# design.net
KiCad netlist of a schematic drawn in Altium Designer
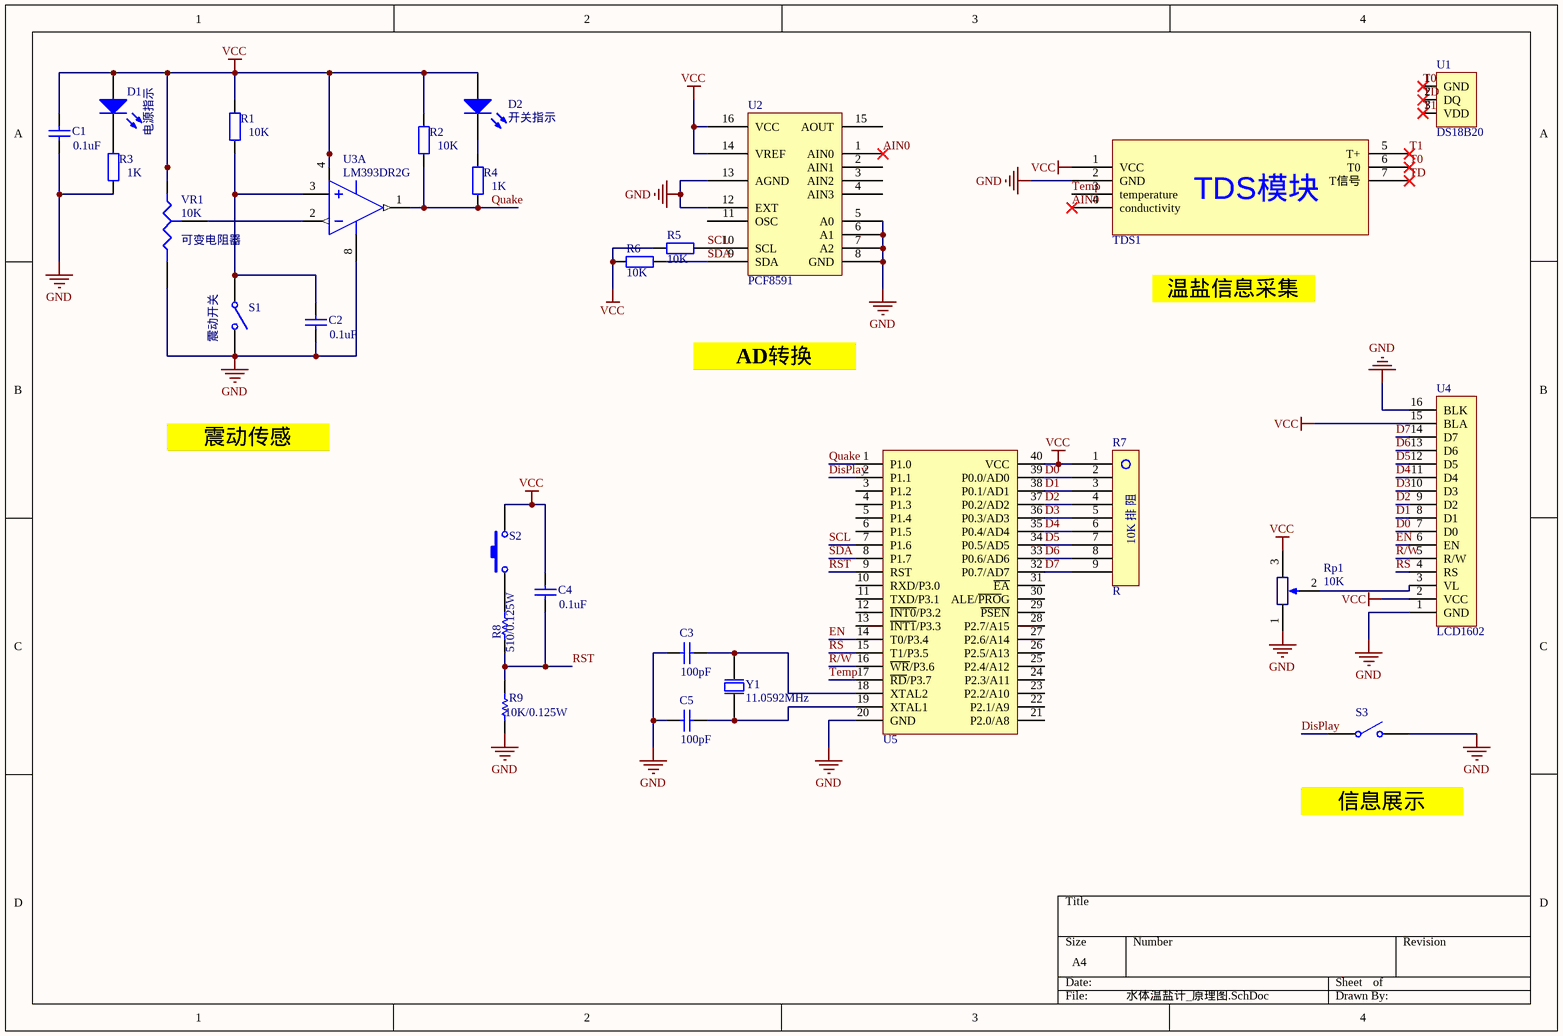
[diagram p0: 水体温盐计_原理图.SchDoc]

(export (version "E")
  (design (tool "Eeschema 10.0.6"))
  (components
    (comp (ref "C1")
      (value "0.1uF")
      (footprint "RAD-0.3")
      (description "Capacitor")
      (fields (field (name "Comment") "Cap") (field (name "PUBLISHER") "Altium Limited"))
      (libsource (lib "Miscellaneous Devices") (part "Cap"))
    )
    (comp (ref "C2")
      (value "0.1uF")
      (footprint "RAD-0.3")
      (description "Capacitor")
      (fields (field (name "Comment") "Cap") (field (name "PUBLISHER") "Altium Limited"))
      (libsource (lib "Miscellaneous Devices") (part "Cap"))
    )
    (comp (ref "C3")
      (value "100pF")
      (footprint "RAD-0.3")
      (description "Capacitor")
      (fields (field (name "Comment") "Cap") (field (name "PUBLISHER") "Altium Limited"))
      (libsource (lib "Miscellaneous Devices") (part "Cap"))
    )
    (comp (ref "C4")
      (value "0.1uF")
      (footprint "RAD-0.3")
      (description "Capacitor")
      (fields (field (name "Comment") "Cap") (field (name "PUBLISHER") "Altium Limited"))
      (libsource (lib "Miscellaneous Devices") (part "Cap"))
    )
    (comp (ref "C5")
      (value "100pF")
      (footprint "RAD-0.3")
      (description "Capacitor")
      (fields (field (name "Comment") "Cap") (field (name "PUBLISHER") "Altium Limited"))
      (libsource (lib "Miscellaneous Devices") (part "Cap"))
    )
    (comp (ref "D1")
      (value "电源指示")
      (footprint "LED-0")
      (description "Typical INFRARED GaAs LED")
      (fields (field (name "PUBLISHER") "Altium Limited"))
      (libsource (lib "Miscellaneous Devices") (part "LED0"))
    )
    (comp (ref "D2")
      (value "开关指示")
      (footprint "3.2X1.6X1.1")
      (description "Typical RED, GREEN, YELLOW, AMBER GaAs LED")
      (fields (field (name "PUBLISHER") "Altium Limited"))
      (libsource (lib "Miscellaneous Devices") (part "LED2"))
    )
    (comp (ref "R1")
      (value "10K")
      (footprint "AXIAL-0.4")
      (description "Resistor")
      (fields (field (name "Comment") "Res2") (field (name "PUBLISHER") "Altium Limited"))
      (libsource (lib "Miscellaneous Devices") (part "Res2"))
    )
    (comp (ref "R2")
      (value "10K")
      (footprint "AXIAL-0.4")
      (description "Resistor")
      (fields (field (name "Comment") "Res2") (field (name "PUBLISHER") "Altium Limited"))
      (libsource (lib "Miscellaneous Devices") (part "Res2"))
    )
    (comp (ref "R3")
      (value "1K")
      (footprint "AXIAL-0.4")
      (description "Resistor")
      (fields (field (name "Comment") "Res2") (field (name "PUBLISHER") "Altium Limited"))
      (libsource (lib "Miscellaneous Devices") (part "Res2"))
    )
    (comp (ref "R4")
      (value "1K")
      (footprint "AXIAL-0.4")
      (description "Resistor")
      (fields (field (name "Comment") "Res2") (field (name "PUBLISHER") "Altium Limited"))
      (libsource (lib "Miscellaneous Devices") (part "Res2"))
    )
    (comp (ref "R5")
      (value "10K")
      (footprint "AXIAL-0.4")
      (description "Resistor")
      (fields (field (name "Comment") "Res2") (field (name "PUBLISHER") "Altium Limited"))
      (libsource (lib "") (part "Res2_1"))
    )
    (comp (ref "R6")
      (value "10K")
      (footprint "AXIAL-0.4")
      (description "Resistor")
      (fields (field (name "Comment") "Res2") (field (name "PUBLISHER") "Altium Limited"))
      (libsource (lib "") (part "Res2_1"))
    )
    (comp (ref "R7") (value "R") (footprint "HDR1X9") (libsource (lib "原理图") (part "R")))
    (comp (ref "R8")
      (value "510/0.125W")
      (footprint "AXIAL-0.3")
      (description "Resistor")
      (fields (field (name "Comment") "Res1") (field (name "PUBLISHER") "Altium Limited"))
      (libsource (lib "Miscellaneous Devices") (part "Res1"))
    )
    (comp (ref "R9")
      (value "10K/0.125W")
      (footprint "AXIAL-0.3")
      (description "Resistor")
      (fields (field (name "Comment") "Res1") (field (name "PUBLISHER") "Altium Limited"))
      (libsource (lib "Miscellaneous Devices") (part "Res1"))
    )
    (comp (ref "Rp1")
      (value "3303X-3-502E")
      (footprint "3303X-3-502E")
      (fields (field (name "R") "10K"))
      (libsource (lib "02 Miscellaneous_Devices_ZSF_Library") (part "RP_3303X-3-502E"))
    )
    (comp (ref "S1")
      (value "震动开关")
      (footprint "SW_3-6-2.5")
      (description "Single-Pole, Single-Throw Switch")
      (fields (field (name "PUBLISHER") "Altium Limited"))
      (libsource (lib "02 Miscellaneous_Devices_ZSF_Library") (part "SW-SPST"))
    )
    (comp (ref "S2")
      (value "Tactile Switch")
      (footprint "BUTTON_6*6")
      (description "Tactile Switch触觉开关")
      (fields (field (name "PUBLISHER") "Altium Limited"))
      (libsource (lib "02 Miscellaneous_Devices_ZSF_Library") (part "SW-PB"))
    )
    (comp (ref "S3")
      (value "S")
      (footprint "SW_3-6-2.5")
      (description "Single-Pole, Single-Throw Switch")
      (fields (field (name "PUBLISHER") "Altium Limited"))
      (libsource (lib "02 Miscellaneous_Devices_ZSF_Library") (part "SW-SPST"))
    )
    (comp (ref "TDS1") (value "TDS水质传感器") (footprint "HDR1X7") (libsource (lib "原理图") (part "TDS水质传感器")))
    (comp (ref "U1")
      (value "DS18B20")
      (footprint "HDR1X3")
      (libsource (lib "02 Miscellaneous_Devices_ZSF_Library") (part "DS18B20"))
    )
    (comp (ref "U2") (value "PCF8591") (footprint "SOT403-1_M") (libsource (lib "原理图") (part "PCF8591")))
    (comp (ref "U3")
      (value "LM393DR2G")
      (footprint "SOIC-8_150mil")
      (description "电压比较器")
      (libsource (lib "02 Miscellaneous_Devices_ZSF_Library") (part "LM393DR2G"))
    )
    (comp (ref "U4")
      (value "LCD1602")
      (footprint "LCD1602")
      (libsource (lib "02 Miscellaneous_Devices_ZSF_Library") (part "LCD1602"))
    )
    (comp (ref "U5")
      (value "AT89C51")
      (footprint "DIP-40")
      (description "AT89C51_DIP40")
      (libsource (lib "02 Miscellaneous_Devices_ZSF_Library") (part "AT89C51-DIP"))
    )
    (comp (ref "VR1")
      (value "可变电阻器")
      (footprint "VR3")
      (description "Tapped Resistor")
      (fields (field (name "ALTIUM_VALUE") "10K") (field (name "PUBLISHER") "Altium Limited"))
      (libsource (lib "Miscellaneous Devices") (part "Res Tap"))
    )
    (comp (ref "Y1")
      (value "XTAL")
      (footprint "XTAL")
      (description "Crystal Oscillator")
      (fields (field (name "FREQUENCY") "11.0592MHz") (field (name "PUBLISHER") "Altium Limited"))
      (libsource (lib "03-EButterflyIntegratedLibrary") (part "XTAL"))
    )
  )
  (nets
    (net (code "1") (name "/AIN0") (class "Default")
      (node (ref "TDS1") (pin "4") (pinfunction "conductivity_4") (pintype "passive"))
      (node (ref "U2") (pin "1") (pinfunction "AIN0_1") (pintype "passive"))
    )
    (net (code "2") (name "/D0") (class "Default")
      (node (ref "R7") (pin "2") (pinfunction "29_2") (pintype "passive"))
      (node (ref "U4") (pin "7") (pinfunction "D0_7") (pintype "passive"))
      (node (ref "U5") (pin "39") (pinfunction "P0.0/AD0_39") (pintype "passive"))
    )
    (net (code "3") (name "/D1") (class "Default")
      (node (ref "R7") (pin "3") (pinfunction "30_3") (pintype "passive"))
      (node (ref "U4") (pin "8") (pinfunction "D1_8") (pintype "passive"))
      (node (ref "U5") (pin "38") (pinfunction "P0.1/AD1_38") (pintype "passive"))
    )
    (net (code "4") (name "/D2") (class "Default")
      (node (ref "R7") (pin "4") (pinfunction "31_4") (pintype "passive"))
      (node (ref "U4") (pin "9") (pinfunction "D2_9") (pintype "passive"))
      (node (ref "U5") (pin "37") (pinfunction "P0.2/AD2_37") (pintype "passive"))
    )
    (net (code "5") (name "/D3") (class "Default")
      (node (ref "R7") (pin "5") (pinfunction "32_5") (pintype "passive"))
      (node (ref "U4") (pin "10") (pinfunction "D3_10") (pintype "passive"))
      (node (ref "U5") (pin "36") (pinfunction "P0.3/AD3_36") (pintype "passive"))
    )
    (net (code "6") (name "/D4") (class "Default")
      (node (ref "R7") (pin "6") (pinfunction "33_6") (pintype "passive"))
      (node (ref "U4") (pin "11") (pinfunction "D4_11") (pintype "passive"))
      (node (ref "U5") (pin "35") (pinfunction "P0.4/AD4_35") (pintype "passive"))
    )
    (net (code "7") (name "/D5") (class "Default")
      (node (ref "R7") (pin "7") (pinfunction "34_7") (pintype "passive"))
      (node (ref "U4") (pin "12") (pinfunction "D5_12") (pintype "passive"))
      (node (ref "U5") (pin "34") (pinfunction "P0.5/AD5_34") (pintype "passive"))
    )
    (net (code "8") (name "/D6") (class "Default")
      (node (ref "R7") (pin "8") (pinfunction "35_8") (pintype "passive"))
      (node (ref "U4") (pin "13") (pinfunction "D6_13") (pintype "passive"))
      (node (ref "U5") (pin "33") (pinfunction "P0.6/AD6_33") (pintype "passive"))
    )
    (net (code "9") (name "/D7") (class "Default")
      (node (ref "R7") (pin "9") (pinfunction "36_9") (pintype "passive"))
      (node (ref "U4") (pin "14") (pinfunction "D7_14") (pintype "passive"))
      (node (ref "U5") (pin "32") (pinfunction "P0.7/AD7_32") (pintype "passive"))
    )
    (net (code "10") (name "/DisPlay") (class "Default")
      (node (ref "S3") (pin "1") (pinfunction "COMMON_1") (pintype "passive"))
      (node (ref "U5") (pin "2") (pinfunction "P1.1_2") (pintype "passive"))
    )
    (net (code "11") (name "/EN") (class "Default")
      (node (ref "U4") (pin "6") (pinfunction "EN_6") (pintype "passive"))
      (node (ref "U5") (pin "14") (pinfunction "T0/P3.4_14") (pintype "passive"))
    )
    (net (code "12") (name "/Quake") (class "Default")
      (node (ref "R2") (pin "1") (pinfunction "1_1") (pintype "passive"))
      (node (ref "R4") (pin "1") (pinfunction "1_1") (pintype "passive"))
      (node (ref "U3") (pin "1") (pinfunction "OUT_1") (pintype "output"))
      (node (ref "U5") (pin "1") (pinfunction "P1.0_1") (pintype "passive"))
    )
    (net (code "13") (name "/RS") (class "Default")
      (node (ref "U4") (pin "4") (pinfunction "RS_4") (pintype "passive"))
      (node (ref "U5") (pin "15") (pinfunction "T1/P3.5_15") (pintype "passive"))
    )
    (net (code "14") (name "/RST") (class "Default")
      (node (ref "C4") (pin "1") (pinfunction "1_1") (pintype "passive"))
      (node (ref "R8") (pin "1") (pinfunction "1_1") (pintype "passive"))
      (node (ref "R9") (pin "2") (pinfunction "2_2") (pintype "passive"))
      (node (ref "U5") (pin "9") (pinfunction "RST_9") (pintype "passive"))
    )
    (net (code "15") (name "/R{slash}W") (class "Default")
      (node (ref "U4") (pin "5") (pinfunction "R/W_5") (pintype "passive"))
      (node (ref "U5") (pin "16") (pinfunction "~{WR}/P3.6_16") (pintype "passive"))
    )
    (net (code "16") (name "/SCL") (class "Default")
      (node (ref "R5") (pin "1") (pinfunction "1_1") (pintype "passive"))
      (node (ref "U2") (pin "10") (pinfunction "SCL_10") (pintype "passive"))
      (node (ref "U5") (pin "7") (pinfunction "P1.6_7") (pintype "passive"))
    )
    (net (code "17") (name "/SDA") (class "Default")
      (node (ref "R6") (pin "1") (pinfunction "1_1") (pintype "passive"))
      (node (ref "U2") (pin "9") (pinfunction "SDA_9") (pintype "passive"))
      (node (ref "U5") (pin "8") (pinfunction "P1.7_8") (pintype "passive"))
    )
    (net (code "18") (name "/T0") (class "Default")
      (node (ref "TDS1") (pin "6") (pinfunction "T0_6") (pintype "passive"))
      (node (ref "U1") (pin "1") (pinfunction "GND_1") (pintype "passive"))
    )
    (net (code "19") (name "/T1") (class "Default")
      (node (ref "TDS1") (pin "5") (pinfunction "T+_5") (pintype "passive"))
      (node (ref "U1") (pin "3") (pinfunction "VDD_3") (pintype "passive"))
    )
    (net (code "20") (name "/TD") (class "Default")
      (node (ref "TDS1") (pin "7") (pinfunction "T信号_7") (pintype "passive"))
      (node (ref "U1") (pin "2") (pinfunction "DQ_2") (pintype "passive"))
    )
    (net (code "21") (name "/Temp") (class "Default")
      (node (ref "TDS1") (pin "3") (pinfunction "temperature_3") (pintype "passive"))
      (node (ref "U5") (pin "17") (pinfunction "~{RD}/P3.7_17") (pintype "passive"))
    )
    (net (code "22") (name "GND") (class "Default")
      (node (ref "C1") (pin "1") (pinfunction "1_1") (pintype "passive"))
      (node (ref "C2") (pin "1") (pinfunction "1_1") (pintype "passive"))
      (node (ref "C3") (pin "1") (pinfunction "1_1") (pintype "passive"))
      (node (ref "C5") (pin "1") (pinfunction "1_1") (pintype "passive"))
      (node (ref "R3") (pin "1") (pinfunction "1_1") (pintype "passive"))
      (node (ref "R9") (pin "1") (pinfunction "1_1") (pintype "passive"))
      (node (ref "Rp1") (pin "1") (pinfunction "1_1") (pintype "passive"))
      (node (ref "S1") (pin "2") (pinfunction "NO_2") (pintype "passive"))
      (node (ref "S3") (pin "2") (pinfunction "NO_2") (pintype "passive"))
      (node (ref "TDS1") (pin "2") (pinfunction "GND_2") (pintype "passive"))
      (node (ref "U2") (pin "12") (pinfunction "EXT_12") (pintype "passive"))
      (node (ref "U2") (pin "13") (pinfunction "AGND_13") (pintype "passive"))
      (node (ref "U2") (pin "5") (pinfunction "A0_5") (pintype "passive"))
      (node (ref "U2") (pin "6") (pinfunction "A1_6") (pintype "passive"))
      (node (ref "U2") (pin "7") (pinfunction "A2_7") (pintype "passive"))
      (node (ref "U2") (pin "8") (pinfunction "GND_8") (pintype "passive"))
      (node (ref "U3") (pin "8") (pinfunction "V+_8") (pintype "power_in"))
      (node (ref "U4") (pin "1") (pinfunction "GND_1") (pintype "passive"))
      (node (ref "U4") (pin "16") (pinfunction "BLK_16") (pintype "passive"))
      (node (ref "U5") (pin "20") (pinfunction "GND_20") (pintype "passive"))
      (node (ref "VR1") (pin "2") (pinfunction "B_2") (pintype "passive"))
    )
    (net (code "23") (name "Net-(D1-K)") (class "Default")
      (node (ref "D1") (pin "2") (pinfunction "K_2") (pintype "passive"))
      (node (ref "R3") (pin "2") (pinfunction "2_2") (pintype "passive"))
    )
    (net (code "24") (name "Net-(D2-K)") (class "Default")
      (node (ref "D2") (pin "2") (pinfunction "K_2") (pintype "passive"))
      (node (ref "R4") (pin "2") (pinfunction "2_2") (pintype "passive"))
    )
    (net (code "25") (name "Net-(R8-Pad2)") (class "Default")
      (node (ref "R8") (pin "2") (pinfunction "2_2") (pintype "passive"))
      (node (ref "S2") (pin "1") (pinfunction "1_1") (pintype "passive"))
    )
    (net (code "26") (name "Net-(S1-COMMON)") (class "Default")
      (node (ref "C2") (pin "2") (pinfunction "2_2") (pintype "passive"))
      (node (ref "R1") (pin "1") (pinfunction "1_1") (pintype "passive"))
      (node (ref "S1") (pin "1") (pinfunction "COMMON_1") (pintype "passive"))
      (node (ref "U3") (pin "3") (pinfunction "IN+_3") (pintype "power_in"))
    )
    (net (code "27") (name "Net-(U3A-IN-)") (class "Default")
      (node (ref "U3") (pin "2") (pinfunction "IN-_2") (pintype "output"))
      (node (ref "VR1") (pin "3") (pinfunction "TAP_3") (pintype "passive"))
    )
    (net (code "28") (name "Net-(U4-VL)") (class "Default")
      (node (ref "Rp1") (pin "2") (pinfunction "2_2") (pintype "passive"))
      (node (ref "U4") (pin "3") (pinfunction "VL_3") (pintype "passive"))
    )
    (net (code "29") (name "Net-(U5-XTAL1)") (class "Default")
      (node (ref "C5") (pin "2") (pinfunction "2_2") (pintype "passive"))
      (node (ref "U5") (pin "19") (pinfunction "XTAL1_19") (pintype "passive"))
      (node (ref "Y1") (pin "1") (pinfunction "OSC1_1") (pintype "passive"))
    )
    (net (code "30") (name "Net-(U5-XTAL2)") (class "Default")
      (node (ref "C3") (pin "2") (pinfunction "2_2") (pintype "passive"))
      (node (ref "U5") (pin "18") (pinfunction "XTAL2_18") (pintype "passive"))
      (node (ref "Y1") (pin "2") (pinfunction "OSC2_2") (pintype "passive"))
    )
    (net (code "31") (name "VCC") (class "Default")
      (node (ref "C1") (pin "2") (pinfunction "2_2") (pintype "passive"))
      (node (ref "C4") (pin "2") (pinfunction "2_2") (pintype "passive"))
      (node (ref "D1") (pin "1") (pinfunction "A_1") (pintype "passive"))
      (node (ref "D2") (pin "1") (pinfunction "A_1") (pintype "passive"))
      (node (ref "R1") (pin "2") (pinfunction "2_2") (pintype "passive"))
      (node (ref "R2") (pin "2") (pinfunction "2_2") (pintype "passive"))
      (node (ref "R5") (pin "2") (pinfunction "2_2") (pintype "passive"))
      (node (ref "R6") (pin "2") (pinfunction "2_2") (pintype "passive"))
      (node (ref "R7") (pin "1") (pinfunction "28_1") (pintype "passive"))
      (node (ref "Rp1") (pin "3") (pinfunction "3_3") (pintype "passive"))
      (node (ref "S2") (pin "2") (pinfunction "2_2") (pintype "passive"))
      (node (ref "TDS1") (pin "1") (pinfunction "VCC_1") (pintype "passive"))
      (node (ref "U2") (pin "14") (pinfunction "VREF_14") (pintype "passive"))
      (node (ref "U2") (pin "16") (pinfunction "VCC_16") (pintype "passive"))
      (node (ref "U3") (pin "4") (pinfunction "GND_4") (pintype "power_in"))
      (node (ref "U4") (pin "15") (pinfunction "BLA_15") (pintype "passive"))
      (node (ref "U4") (pin "2") (pinfunction "VCC_2") (pintype "passive"))
      (node (ref "U5") (pin "40") (pinfunction "VCC_40") (pintype "passive"))
      (node (ref "VR1") (pin "1") (pinfunction "A_1") (pintype "passive"))
    )
    (net (code "32") (name "unconnected-(U2-AIN1-Pad2)") (class "Default")
      (node (ref "U2") (pin "2") (pinfunction "AIN1_2") (pintype "passive"))
    )
    (net (code "33") (name "unconnected-(U2-AIN2-Pad3)") (class "Default")
      (node (ref "U2") (pin "3") (pinfunction "AIN2_3") (pintype "passive"))
    )
    (net (code "34") (name "unconnected-(U2-AIN3-Pad4)") (class "Default")
      (node (ref "U2") (pin "4") (pinfunction "AIN3_4") (pintype "passive"))
    )
    (net (code "35") (name "unconnected-(U2-AOUT-Pad15)") (class "Default")
      (node (ref "U2") (pin "15") (pinfunction "AOUT_15") (pintype "passive"))
    )
    (net (code "36") (name "unconnected-(U2-OSC-Pad11)") (class "Default")
      (node (ref "U2") (pin "11") (pinfunction "OSC_11") (pintype "passive"))
    )
    (net (code "37") (name "unconnected-(U5-ALE{slash}~{PRO}G-Pad30)") (class "Default")
      (node (ref "U5") (pin "30") (pinfunction "ALE/~{PRO}G_30") (pintype "passive"))
    )
    (net (code "38") (name "unconnected-(U5-P1.2-Pad3)") (class "Default")
      (node (ref "U5") (pin "3") (pinfunction "P1.2_3") (pintype "passive"))
    )
    (net (code "39") (name "unconnected-(U5-P1.3-Pad4)") (class "Default")
      (node (ref "U5") (pin "4") (pinfunction "P1.3_4") (pintype "passive"))
    )
    (net (code "40") (name "unconnected-(U5-P1.4-Pad5)") (class "Default")
      (node (ref "U5") (pin "5") (pinfunction "P1.4_5") (pintype "passive"))
    )
    (net (code "41") (name "unconnected-(U5-P1.5-Pad6)") (class "Default")
      (node (ref "U5") (pin "6") (pinfunction "P1.5_6") (pintype "passive"))
    )
    (net (code "42") (name "unconnected-(U5-P2.0{slash}A8-Pad21)") (class "Default")
      (node (ref "U5") (pin "21") (pinfunction "P2.0/A8_21") (pintype "passive"))
    )
    (net (code "43") (name "unconnected-(U5-P2.1{slash}A9-Pad22)") (class "Default")
      (node (ref "U5") (pin "22") (pinfunction "P2.1/A9_22") (pintype "passive"))
    )
    (net (code "44") (name "unconnected-(U5-P2.2{slash}A10-Pad23)") (class "Default")
      (node (ref "U5") (pin "23") (pinfunction "P2.2/A10_23") (pintype "passive"))
    )
    (net (code "45") (name "unconnected-(U5-P2.3{slash}A11-Pad24)") (class "Default")
      (node (ref "U5") (pin "24") (pinfunction "P2.3/A11_24") (pintype "passive"))
    )
    (net (code "46") (name "unconnected-(U5-P2.4{slash}A12-Pad25)") (class "Default")
      (node (ref "U5") (pin "25") (pinfunction "P2.4/A12_25") (pintype "passive"))
    )
    (net (code "47") (name "unconnected-(U5-P2.5{slash}A13-Pad26)") (class "Default")
      (node (ref "U5") (pin "26") (pinfunction "P2.5/A13_26") (pintype "passive"))
    )
    (net (code "48") (name "unconnected-(U5-P2.6{slash}A14-Pad27)") (class "Default")
      (node (ref "U5") (pin "27") (pinfunction "P2.6/A14_27") (pintype "passive"))
    )
    (net (code "49") (name "unconnected-(U5-P2.7{slash}A15-Pad28)") (class "Default")
      (node (ref "U5") (pin "28") (pinfunction "P2.7/A15_28") (pintype "passive"))
    )
    (net (code "50") (name "unconnected-(U5-RXD{slash}P3.0-Pad10)") (class "Default")
      (node (ref "U5") (pin "10") (pinfunction "RXD/P3.0_10") (pintype "passive"))
    )
    (net (code "51") (name "unconnected-(U5-TXD{slash}P3.1-Pad11)") (class "Default")
      (node (ref "U5") (pin "11") (pinfunction "TXD/P3.1_11") (pintype "passive"))
    )
    (net (code "52") (name "unconnected-(U5-~{EA}-Pad31)") (class "Default")
      (node (ref "U5") (pin "31") (pinfunction "~{EA}_31") (pintype "passive"))
    )
    (net (code "53") (name "unconnected-(U5-~{INT0}{slash}P3.2-Pad12)") (class "Default")
      (node (ref "U5") (pin "12") (pinfunction "~{INT0}/P3.2_12") (pintype "passive"))
    )
    (net (code "54") (name "unconnected-(U5-~{INT1}{slash}P3.3-Pad13)") (class "Default")
      (node (ref "U5") (pin "13") (pinfunction "~{INT1}/P3.3_13") (pintype "passive"))
    )
    (net (code "55") (name "unconnected-(U5-~{PSEN}-Pad29)") (class "Default")
      (node (ref "U5") (pin "29") (pinfunction "~{PSEN}_29") (pintype "passive"))
    )
  )
)
